# Interface.net
KiCad netlist of a schematic drawn in Altium Designer
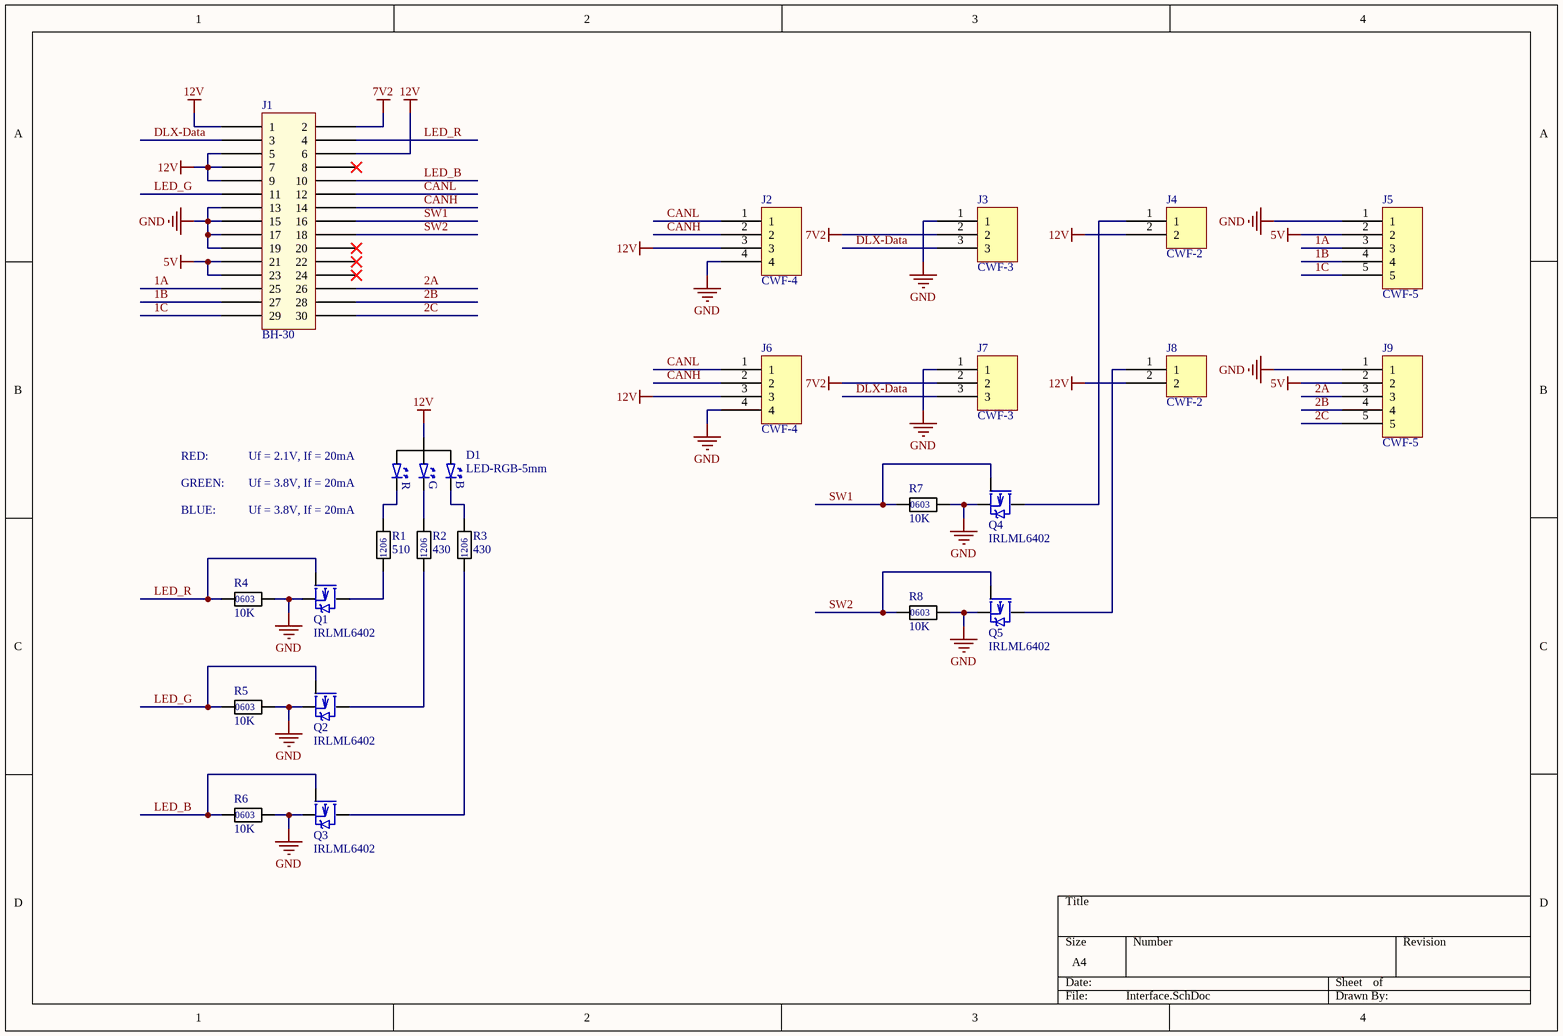
[diagram p0: Interface.SchDoc]

(export (version "E")
  (design (tool "Eeschema 10.0.6"))
  (components
    (comp (ref "D1")
      (value "LED-RGB-5mm")
      (footprint "BL-L515")
      (libsource (lib "Popular") (part "LED-RGB-5mm"))
    )
    (comp (ref "J1") (value "BH-30") (footprint "BH-30") (libsource (lib "Popular") (part "BH-30")))
    (comp (ref "J2")
      (value "CWF-4")
      (footprint "CWF-4")
      (description "Connector")
      (libsource (lib "Popular") (part "CWF-4"))
    )
    (comp (ref "J3")
      (value "CWF-3")
      (footprint "DS1066-03")
      (description "Conector")
      (libsource (lib "Popular") (part "CWF-3(R)"))
    )
    (comp (ref "J4")
      (value "CWF-2")
      (footprint "CWF-2")
      (description "Connector")
      (libsource (lib "Popular") (part "CWF-2"))
    )
    (comp (ref "J5") (value "CWF-5") (footprint "CWF-5") (libsource (lib "Popular") (part "CWF-5")))
    (comp (ref "J6")
      (value "CWF-4")
      (footprint "CWF-4")
      (description "Connector")
      (libsource (lib "Popular") (part "CWF-4"))
    )
    (comp (ref "J7")
      (value "CWF-3")
      (footprint "DS1066-03")
      (description "Conector")
      (libsource (lib "Popular") (part "CWF-3(R)"))
    )
    (comp (ref "J8")
      (value "CWF-2")
      (footprint "CWF-2")
      (description "Connector")
      (libsource (lib "Popular") (part "CWF-2"))
    )
    (comp (ref "J9") (value "CWF-5") (footprint "CWF-5") (libsource (lib "Popular") (part "CWF-5")))
    (comp (ref "Q1")
      (value "IRLML6402")
      (footprint "SOT23")
      (description "p-chanal MOSFET")
      (libsource (lib "Popular") (part "IRLML6402"))
    )
    (comp (ref "Q2")
      (value "IRLML6402")
      (footprint "SOT23")
      (description "p-chanal MOSFET")
      (libsource (lib "Popular") (part "IRLML6402"))
    )
    (comp (ref "Q3")
      (value "IRLML6402")
      (footprint "SOT23")
      (description "p-chanal MOSFET")
      (libsource (lib "Popular") (part "IRLML6402"))
    )
    (comp (ref "Q4")
      (value "IRLML6402")
      (footprint "SOT23")
      (description "p-chanal MOSFET")
      (libsource (lib "Popular") (part "IRLML6402"))
    )
    (comp (ref "Q5")
      (value "IRLML6402")
      (footprint "SOT23")
      (description "p-chanal MOSFET")
      (libsource (lib "Popular") (part "IRLML6402"))
    )
    (comp (ref "R1")
      (value "510")
      (footprint "CHIP_R_1206")
      (description "Resistor")
      (libsource (lib "Popular") (part "RES_1206"))
    )
    (comp (ref "R2")
      (value "430")
      (footprint "CHIP_R_1206")
      (description "Resistor")
      (libsource (lib "Popular") (part "RES_1206"))
    )
    (comp (ref "R3")
      (value "430")
      (footprint "CHIP_R_1206")
      (description "Resistor")
      (libsource (lib "Popular") (part "RES_1206"))
    )
    (comp (ref "R4") (value "10K") (footprint "CHIP_R_0603") (libsource (lib "Popular") (part "RES_0603")))
    (comp (ref "R5") (value "10K") (footprint "CHIP_R_0603") (libsource (lib "Popular") (part "RES_0603")))
    (comp (ref "R6") (value "10K") (footprint "CHIP_R_0603") (libsource (lib "Popular") (part "RES_0603")))
    (comp (ref "R7") (value "10K") (footprint "CHIP_R_0603") (libsource (lib "Popular") (part "RES_0603")))
    (comp (ref "R8") (value "10K") (footprint "CHIP_R_0603") (libsource (lib "Popular") (part "RES_0603")))
  )
  (nets
    (net (code "1") (name "/1A") (class "Default")
      (node (ref "J1") (pin "25") (pinfunction "25_25") (pintype "passive"))
      (node (ref "J5") (pin "3") (pinfunction "3_3") (pintype "passive"))
    )
    (net (code "2") (name "/1B") (class "Default")
      (node (ref "J1") (pin "27") (pinfunction "27_27") (pintype "passive"))
      (node (ref "J5") (pin "4") (pinfunction "4_4") (pintype "passive"))
    )
    (net (code "3") (name "/1C") (class "Default")
      (node (ref "J1") (pin "29") (pinfunction "29_29") (pintype "passive"))
      (node (ref "J5") (pin "5") (pinfunction "5_5") (pintype "passive"))
    )
    (net (code "4") (name "/2A") (class "Default")
      (node (ref "J1") (pin "26") (pinfunction "26_26") (pintype "passive"))
      (node (ref "J9") (pin "3") (pinfunction "3_3") (pintype "passive"))
    )
    (net (code "5") (name "/2B") (class "Default")
      (node (ref "J1") (pin "28") (pinfunction "28_28") (pintype "passive"))
      (node (ref "J9") (pin "4") (pinfunction "4_4") (pintype "passive"))
    )
    (net (code "6") (name "/2C") (class "Default")
      (node (ref "J1") (pin "30") (pinfunction "30_30") (pintype "passive"))
      (node (ref "J9") (pin "5") (pinfunction "5_5") (pintype "passive"))
    )
    (net (code "7") (name "/CANH") (class "Default")
      (node (ref "J1") (pin "14") (pinfunction "14_14") (pintype "passive"))
      (node (ref "J2") (pin "2") (pinfunction "2_2") (pintype "passive"))
      (node (ref "J6") (pin "2") (pinfunction "2_2") (pintype "passive"))
    )
    (net (code "8") (name "/CANL") (class "Default")
      (node (ref "J1") (pin "12") (pinfunction "12_12") (pintype "passive"))
      (node (ref "J2") (pin "1") (pinfunction "1_1") (pintype "passive"))
      (node (ref "J6") (pin "1") (pinfunction "1_1") (pintype "passive"))
    )
    (net (code "9") (name "/DLX-Data") (class "Default")
      (node (ref "J1") (pin "3") (pinfunction "3_3") (pintype "passive"))
      (node (ref "J3") (pin "3") (pinfunction "3_3") (pintype "passive"))
      (node (ref "J7") (pin "3") (pinfunction "3_3") (pintype "passive"))
    )
    (net (code "10") (name "/LED_B") (class "Default")
      (node (ref "J1") (pin "10") (pinfunction "10_10") (pintype "passive"))
      (node (ref "Q3") (pin "1") (pinfunction "G_1") (pintype "passive"))
      (node (ref "R6") (pin "1") (pinfunction "1_1") (pintype "passive"))
    )
    (net (code "11") (name "/LED_G") (class "Default")
      (node (ref "J1") (pin "11") (pinfunction "11_11") (pintype "passive"))
      (node (ref "Q2") (pin "1") (pinfunction "G_1") (pintype "passive"))
      (node (ref "R5") (pin "1") (pinfunction "1_1") (pintype "passive"))
    )
    (net (code "12") (name "/LED_R") (class "Default")
      (node (ref "J1") (pin "4") (pinfunction "4_4") (pintype "passive"))
      (node (ref "Q1") (pin "1") (pinfunction "G_1") (pintype "passive"))
      (node (ref "R4") (pin "1") (pinfunction "1_1") (pintype "passive"))
    )
    (net (code "13") (name "/SW1") (class "Default")
      (node (ref "J1") (pin "16") (pinfunction "16_16") (pintype "passive"))
      (node (ref "Q4") (pin "1") (pinfunction "G_1") (pintype "passive"))
      (node (ref "R7") (pin "1") (pinfunction "1_1") (pintype "passive"))
    )
    (net (code "14") (name "/SW2") (class "Default")
      (node (ref "J1") (pin "18") (pinfunction "18_18") (pintype "passive"))
      (node (ref "Q5") (pin "1") (pinfunction "G_1") (pintype "passive"))
      (node (ref "R8") (pin "1") (pinfunction "1_1") (pintype "passive"))
    )
    (net (code "15") (name "5V") (class "Default")
      (node (ref "J1") (pin "21") (pinfunction "21_21") (pintype "passive"))
      (node (ref "J1") (pin "23") (pinfunction "23_23") (pintype "passive"))
      (node (ref "J5") (pin "2") (pinfunction "2_2") (pintype "passive"))
      (node (ref "J9") (pin "2") (pinfunction "2_2") (pintype "passive"))
    )
    (net (code "16") (name "7V2") (class "Default")
      (node (ref "J1") (pin "2") (pinfunction "2_2") (pintype "passive"))
      (node (ref "J3") (pin "2") (pinfunction "2_2") (pintype "passive"))
      (node (ref "J7") (pin "2") (pinfunction "2_2") (pintype "passive"))
    )
    (net (code "17") (name "12V") (class "Default")
      (node (ref "D1") (pin "3") (pinfunction "A_3") (pintype "passive"))
      (node (ref "J1") (pin "1") (pinfunction "1_1") (pintype "passive"))
      (node (ref "J1") (pin "5") (pinfunction "5_5") (pintype "passive"))
      (node (ref "J1") (pin "6") (pinfunction "6_6") (pintype "passive"))
      (node (ref "J1") (pin "7") (pinfunction "7_7") (pintype "passive"))
      (node (ref "J1") (pin "9") (pinfunction "9_9") (pintype "passive"))
      (node (ref "J2") (pin "3") (pinfunction "3_3") (pintype "passive"))
      (node (ref "J4") (pin "2") (pinfunction "2_2") (pintype "passive"))
      (node (ref "J6") (pin "3") (pinfunction "3_3") (pintype "passive"))
      (node (ref "J8") (pin "2") (pinfunction "2_2") (pintype "passive"))
    )
    (net (code "18") (name "GND") (class "Default")
      (node (ref "J1") (pin "13") (pinfunction "13_13") (pintype "passive"))
      (node (ref "J1") (pin "15") (pinfunction "15_15") (pintype "passive"))
      (node (ref "J1") (pin "17") (pinfunction "17_17") (pintype "passive"))
      (node (ref "J1") (pin "19") (pinfunction "19_19") (pintype "passive"))
      (node (ref "J2") (pin "4") (pinfunction "4_4") (pintype "passive"))
      (node (ref "J3") (pin "1") (pinfunction "1_1") (pintype "passive"))
      (node (ref "J5") (pin "1") (pinfunction "1_1") (pintype "passive"))
      (node (ref "J6") (pin "4") (pinfunction "4_4") (pintype "passive"))
      (node (ref "J7") (pin "1") (pinfunction "1_1") (pintype "passive"))
      (node (ref "J9") (pin "1") (pinfunction "1_1") (pintype "passive"))
      (node (ref "Q1") (pin "2") (pinfunction "S_2") (pintype "passive"))
      (node (ref "Q2") (pin "2") (pinfunction "S_2") (pintype "passive"))
      (node (ref "Q3") (pin "2") (pinfunction "S_2") (pintype "passive"))
      (node (ref "Q4") (pin "2") (pinfunction "S_2") (pintype "passive"))
      (node (ref "Q5") (pin "2") (pinfunction "S_2") (pintype "passive"))
      (node (ref "R4") (pin "2") (pinfunction "2_2") (pintype "passive"))
      (node (ref "R5") (pin "2") (pinfunction "2_2") (pintype "passive"))
      (node (ref "R6") (pin "2") (pinfunction "2_2") (pintype "passive"))
      (node (ref "R7") (pin "2") (pinfunction "2_2") (pintype "passive"))
      (node (ref "R8") (pin "2") (pinfunction "2_2") (pintype "passive"))
    )
    (net (code "19") (name "Net-(D1-B)") (class "Default")
      (node (ref "D1") (pin "1") (pinfunction "B_1") (pintype "passive"))
      (node (ref "R3") (pin "2") (pinfunction "2_2") (pintype "passive"))
    )
    (net (code "20") (name "Net-(D1-G)") (class "Default")
      (node (ref "D1") (pin "2") (pinfunction "G_2") (pintype "passive"))
      (node (ref "R2") (pin "2") (pinfunction "2_2") (pintype "passive"))
    )
    (net (code "21") (name "Net-(D1-R)") (class "Default")
      (node (ref "D1") (pin "4") (pinfunction "R_4") (pintype "passive"))
      (node (ref "R1") (pin "2") (pinfunction "2_2") (pintype "passive"))
    )
    (net (code "22") (name "Net-(Q1-D)") (class "Default")
      (node (ref "Q1") (pin "3") (pinfunction "D_3") (pintype "passive"))
      (node (ref "R1") (pin "1") (pinfunction "1_1") (pintype "passive"))
    )
    (net (code "23") (name "Net-(Q2-D)") (class "Default")
      (node (ref "Q2") (pin "3") (pinfunction "D_3") (pintype "passive"))
      (node (ref "R2") (pin "1") (pinfunction "1_1") (pintype "passive"))
    )
    (net (code "24") (name "Net-(Q3-D)") (class "Default")
      (node (ref "Q3") (pin "3") (pinfunction "D_3") (pintype "passive"))
      (node (ref "R3") (pin "1") (pinfunction "1_1") (pintype "passive"))
    )
    (net (code "25") (name "Net-(Q4-D)") (class "Default")
      (node (ref "J4") (pin "1") (pinfunction "1_1") (pintype "passive"))
      (node (ref "Q4") (pin "3") (pinfunction "D_3") (pintype "passive"))
    )
    (net (code "26") (name "Net-(Q5-D)") (class "Default")
      (node (ref "J8") (pin "1") (pinfunction "1_1") (pintype "passive"))
      (node (ref "Q5") (pin "3") (pinfunction "D_3") (pintype "passive"))
    )
    (net (code "27") (name "unconnected-(J1-Pad8)") (class "Default")
      (node (ref "J1") (pin "8") (pinfunction "8_8") (pintype "passive+no_connect"))
    )
    (net (code "28") (name "unconnected-(J1-Pad20)") (class "Default")
      (node (ref "J1") (pin "20") (pinfunction "20_20") (pintype "passive+no_connect"))
    )
    (net (code "29") (name "unconnected-(J1-Pad22)") (class "Default")
      (node (ref "J1") (pin "22") (pinfunction "22_22") (pintype "passive+no_connect"))
    )
    (net (code "30") (name "unconnected-(J1-Pad24)") (class "Default")
      (node (ref "J1") (pin "24") (pinfunction "24_24") (pintype "passive+no_connect"))
    )
  )
)
